# Dual_Channel.net
KiCad netlist of a schematic drawn in Altium Designer
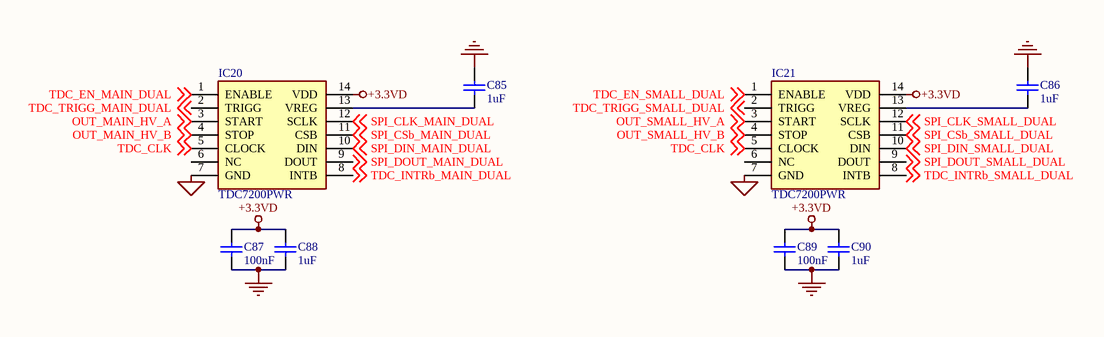
[diagram p0: Dual_Channel.SchDoc]

(export (version "E")
  (design (tool "Eeschema 10.0.6"))
  (components
    (comp (ref "C85")
      (value "1uF")
      (footprint "CAPC1608X90X35ML10T15")
      (description "0603")
      (fields (field (name "MANUFACTURER") "Murata"))
      (libsource (lib "Altium Content Vault") (part "CAP-NP-2"))
    )
    (comp (ref "C86")
      (value "1uF")
      (footprint "CAPC1608X90X35ML10T15")
      (description "0603")
      (fields (field (name "MANUFACTURER") "Murata"))
      (libsource (lib "Altium Content Vault") (part "CAP-NP-2"))
    )
    (comp (ref "C87")
      (value "100nF")
      (footprint "CAPC1608X90X35ML10T15")
      (description "0603")
      (fields (field (name "MANUFACTURER") "Murata"))
      (libsource (lib "Altium Content Vault") (part "CAP-NP-2"))
    )
    (comp (ref "C88")
      (value "1uF")
      (footprint "CAPC1608X90X35ML10T15")
      (description "0603")
      (fields (field (name "MANUFACTURER") "Murata"))
      (libsource (lib "Altium Content Vault") (part "CAP-NP-2"))
    )
    (comp (ref "C89")
      (value "100nF")
      (footprint "CAPC1608X90X35ML10T15")
      (description "0603")
      (fields (field (name "MANUFACTURER") "Murata"))
      (libsource (lib "Altium Content Vault") (part "CAP-NP-2"))
    )
    (comp (ref "C90")
      (value "1uF")
      (footprint "CAPC1608X90X35ML10T15")
      (description "0603")
      (fields (field (name "MANUFACTURER") "Murata"))
      (libsource (lib "Altium Content Vault") (part "CAP-NP-2"))
    )
    (comp (ref "IC20")
      (value "TDC7200PWR")
      (footprint "SamacSys:SOP65P640X120-14N")
      (description "Integrated Circuit")
      (libsource (lib "*") (part "TDC7200PWR"))
    )
    (comp (ref "IC21")
      (value "TDC7200PWR")
      (footprint "SamacSys:SOP65P640X120-14N")
      (description "Integrated Circuit")
      (libsource (lib "*") (part "TDC7200PWR"))
    )
  )
  (nets
    (net (code "1") (name "+3.3VD") (class "Default")
      (node (ref "C87") (pin "1") (pinfunction "1_1") (pintype "passive"))
      (node (ref "C88") (pin "1") (pinfunction "1_1") (pintype "passive"))
      (node (ref "C89") (pin "1") (pinfunction "1_1") (pintype "passive"))
      (node (ref "C90") (pin "1") (pinfunction "1_1") (pintype "passive"))
      (node (ref "IC20") (pin "14") (pinfunction "VDD_14") (pintype "passive"))
      (node (ref "IC21") (pin "14") (pinfunction "VDD_14") (pintype "passive"))
    )
    (net (code "2") (name "GND") (class "Default")
      (node (ref "C85") (pin "2") (pinfunction "2_2") (pintype "passive"))
      (node (ref "C86") (pin "2") (pinfunction "2_2") (pintype "passive"))
      (node (ref "C87") (pin "2") (pinfunction "2_2") (pintype "passive"))
      (node (ref "C88") (pin "2") (pinfunction "2_2") (pintype "passive"))
      (node (ref "C89") (pin "2") (pinfunction "2_2") (pintype "passive"))
      (node (ref "C90") (pin "2") (pinfunction "2_2") (pintype "passive"))
      (node (ref "IC20") (pin "7") (pinfunction "GND_7") (pintype "passive"))
      (node (ref "IC21") (pin "7") (pinfunction "GND_7") (pintype "passive"))
    )
    (net (code "3") (name "Net-(IC20-VREG)") (class "Default")
      (node (ref "C85") (pin "1") (pinfunction "1_1") (pintype "passive"))
      (node (ref "IC20") (pin "13") (pinfunction "VREG_13") (pintype "passive"))
    )
    (net (code "4") (name "Net-(IC21-VREG)") (class "Default")
      (node (ref "C86") (pin "1") (pinfunction "1_1") (pintype "passive"))
      (node (ref "IC21") (pin "13") (pinfunction "VREG_13") (pintype "passive"))
    )
    (net (code "5") (name "OUT_MAIN_HV_A") (class "Default")
      (node (ref "IC20") (pin "3") (pinfunction "START_3") (pintype "passive"))
    )
    (net (code "6") (name "OUT_MAIN_HV_B") (class "Default")
      (node (ref "IC20") (pin "4") (pinfunction "STOP_4") (pintype "passive"))
    )
    (net (code "7") (name "OUT_SMALL_HV_A") (class "Default")
      (node (ref "IC21") (pin "3") (pinfunction "START_3") (pintype "passive"))
    )
    (net (code "8") (name "OUT_SMALL_HV_B") (class "Default")
      (node (ref "IC21") (pin "4") (pinfunction "STOP_4") (pintype "passive"))
    )
    (net (code "9") (name "SPI_CLK_MAIN_DUAL") (class "Default")
      (node (ref "IC20") (pin "12") (pinfunction "SCLK_12") (pintype "passive"))
    )
    (net (code "10") (name "SPI_CLK_SMALL_DUAL") (class "Default")
      (node (ref "IC21") (pin "12") (pinfunction "SCLK_12") (pintype "passive"))
    )
    (net (code "11") (name "SPI_CSb_MAIN_DUAL") (class "Default")
      (node (ref "IC20") (pin "11") (pinfunction "CSB_11") (pintype "passive"))
    )
    (net (code "12") (name "SPI_CSb_SMALL_DUAL") (class "Default")
      (node (ref "IC21") (pin "11") (pinfunction "CSB_11") (pintype "passive"))
    )
    (net (code "13") (name "SPI_DIN_MAIN_DUAL") (class "Default")
      (node (ref "IC20") (pin "10") (pinfunction "DIN_10") (pintype "passive"))
    )
    (net (code "14") (name "SPI_DIN_SMALL_DUAL") (class "Default")
      (node (ref "IC21") (pin "10") (pinfunction "DIN_10") (pintype "passive"))
    )
    (net (code "15") (name "SPI_DOUT_MAIN_DUAL") (class "Default")
      (node (ref "IC20") (pin "9") (pinfunction "DOUT_9") (pintype "passive"))
    )
    (net (code "16") (name "SPI_DOUT_SMALL_DUAL") (class "Default")
      (node (ref "IC21") (pin "9") (pinfunction "DOUT_9") (pintype "passive"))
    )
    (net (code "17") (name "TDC_CLK") (class "Default")
      (node (ref "IC20") (pin "5") (pinfunction "CLOCK_5") (pintype "passive"))
      (node (ref "IC21") (pin "5") (pinfunction "CLOCK_5") (pintype "passive"))
    )
    (net (code "18") (name "TDC_EN_MAIN_DUAL") (class "Default")
      (node (ref "IC20") (pin "1") (pinfunction "ENABLE_1") (pintype "passive"))
    )
    (net (code "19") (name "TDC_EN_SMALL_DUAL") (class "Default")
      (node (ref "IC21") (pin "1") (pinfunction "ENABLE_1") (pintype "passive"))
    )
    (net (code "20") (name "TDC_INTRb_MAIN_DUAL") (class "Default")
      (node (ref "IC20") (pin "8") (pinfunction "INTB_8") (pintype "passive"))
    )
    (net (code "21") (name "TDC_INTRb_SMALL_DUAL") (class "Default")
      (node (ref "IC21") (pin "8") (pinfunction "INTB_8") (pintype "passive"))
    )
    (net (code "22") (name "TDC_TRIGG_MAIN_DUAL") (class "Default")
      (node (ref "IC20") (pin "2") (pinfunction "TRIGG_2") (pintype "passive"))
    )
    (net (code "23") (name "TDC_TRIGG_SMALL_DUAL") (class "Default")
      (node (ref "IC21") (pin "2") (pinfunction "TRIGG_2") (pintype "passive"))
    )
    (net (code "24") (name "unconnected-(IC20-NC-Pad6)") (class "Default")
      (node (ref "IC20") (pin "6") (pinfunction "NC_6") (pintype "passive"))
    )
    (net (code "25") (name "unconnected-(IC21-NC-Pad6)") (class "Default")
      (node (ref "IC21") (pin "6") (pinfunction "NC_6") (pintype "passive"))
    )
  )
)
